# Eurorack_Gate_In.net
KiCad netlist of a schematic drawn in EAGLE
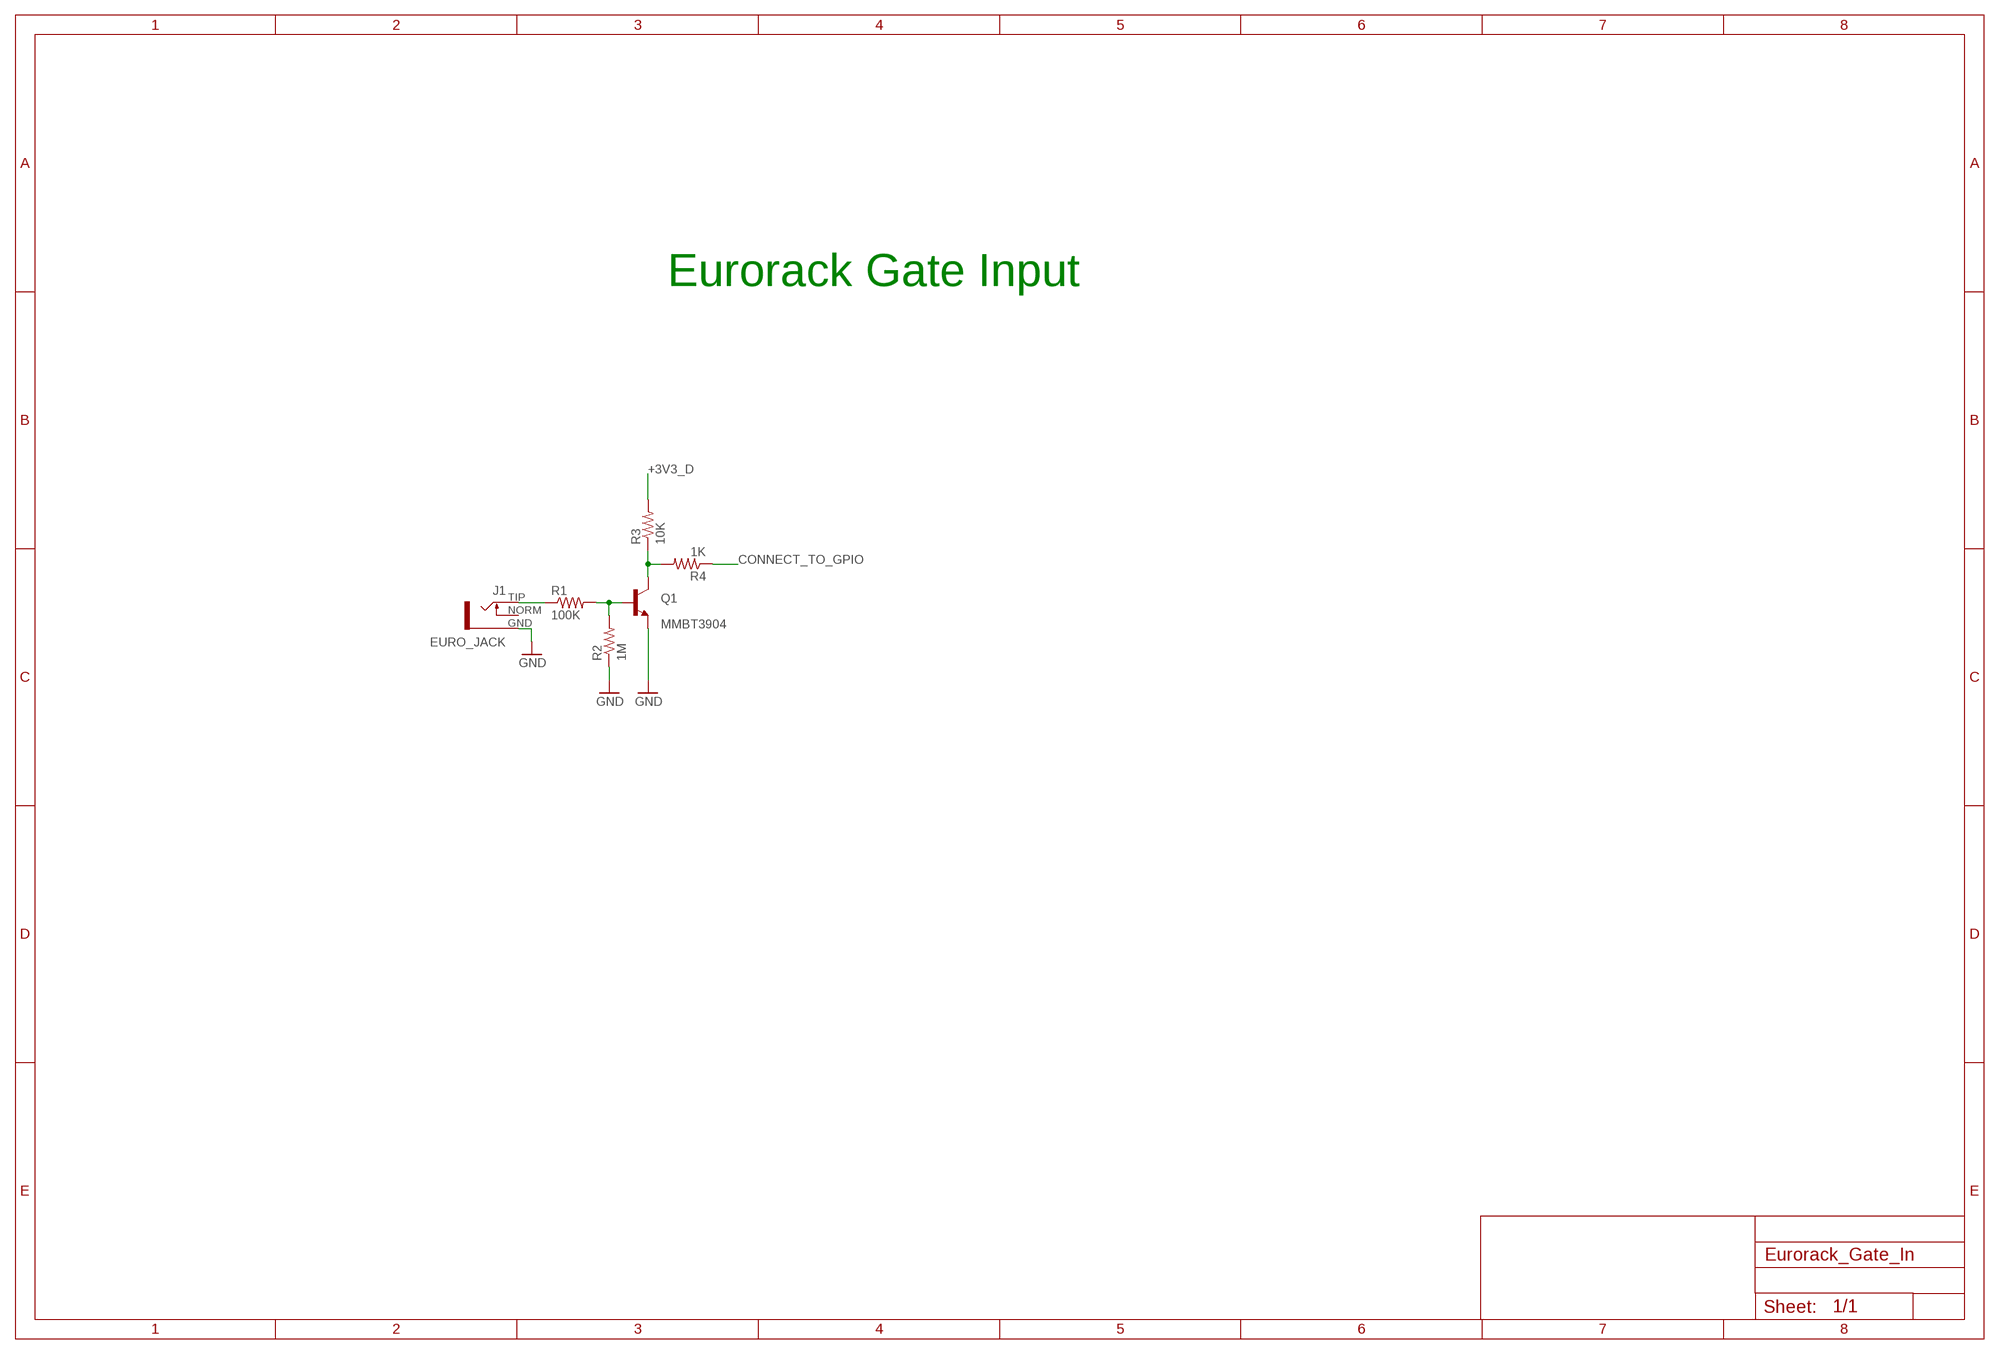
[diagram p0: schematic, sheet 1]

(export (version "E")
  (design (tool "Eeschema 10.0.6"))
  (components
    (comp (ref "J1")
      (value "EURO_JACK")
      (footprint "eagle-import:S_JACK")
      (libsource (lib "eagle-import") (part "EURO_JACK"))
    )
    (comp (ref "Q1")
      (value "MMBT3904")
      (footprint "eagle-import:SOT23-BEC")
      (libsource (lib "eagle-import") (part "NPNSOT23-BEC"))
    )
    (comp (ref "R1")
      (value "100K")
      (footprint "eagle-import:R0603")
      (libsource (lib "eagle-import") (part "R-US_R0603"))
    )
    (comp (ref "R2")
      (value "1M")
      (footprint "eagle-import:R0603")
      (libsource (lib "eagle-import") (part "R-US_R0603"))
    )
    (comp (ref "R3")
      (value "10K")
      (footprint "eagle-import:R0603")
      (libsource (lib "eagle-import") (part "R-US_R0603"))
    )
    (comp (ref "R4")
      (value "1K")
      (footprint "eagle-import:R0603")
      (libsource (lib "eagle-import") (part "R-US_R0603"))
    )
  )
  (nets
    (net (code "1") (name "/+3V3_D") (class "Default")
      (node (ref "R3") (pin "2") (pinfunction "2_2") (pintype "passive"))
    )
    (net (code "2") (name "/CONNECT_TO_GPIO") (class "Default")
      (node (ref "R4") (pin "1") (pinfunction "1_1") (pintype "passive"))
    )
    (net (code "3") (name "GND") (class "Default")
      (node (ref "J1") (pin "GND") (pinfunction "GND_GND") (pintype "passive"))
      (node (ref "Q1") (pin "E") (pinfunction "E_E") (pintype "passive"))
      (node (ref "R2") (pin "1") (pinfunction "1_1") (pintype "passive"))
    )
    (net (code "4") (name "Net-(J1-PadTIP)") (class "Default")
      (node (ref "J1") (pin "TIP") (pinfunction "TIP_TIP") (pintype "passive"))
      (node (ref "R1") (pin "1") (pinfunction "1_1") (pintype "passive"))
    )
    (net (code "5") (name "Net-(Q1-PadB)") (class "Default")
      (node (ref "Q1") (pin "B") (pinfunction "B_B") (pintype "passive"))
      (node (ref "R1") (pin "2") (pinfunction "2_2") (pintype "passive"))
      (node (ref "R2") (pin "2") (pinfunction "2_2") (pintype "passive"))
    )
    (net (code "6") (name "Net-(Q1-PadC)") (class "Default")
      (node (ref "Q1") (pin "C") (pinfunction "C_C") (pintype "passive"))
      (node (ref "R3") (pin "1") (pinfunction "1_1") (pintype "passive"))
      (node (ref "R4") (pin "2") (pinfunction "2_2") (pintype "passive"))
    )
    (net (code "7") (name "unconnected-(J1-PadNORM)") (class "Default")
      (node (ref "J1") (pin "NORM") (pinfunction "NORM_NORM") (pintype "passive"))
    )
  )
)
